# Task_10_1DHD.net
KiCad netlist of a schematic drawn in EasyEDA
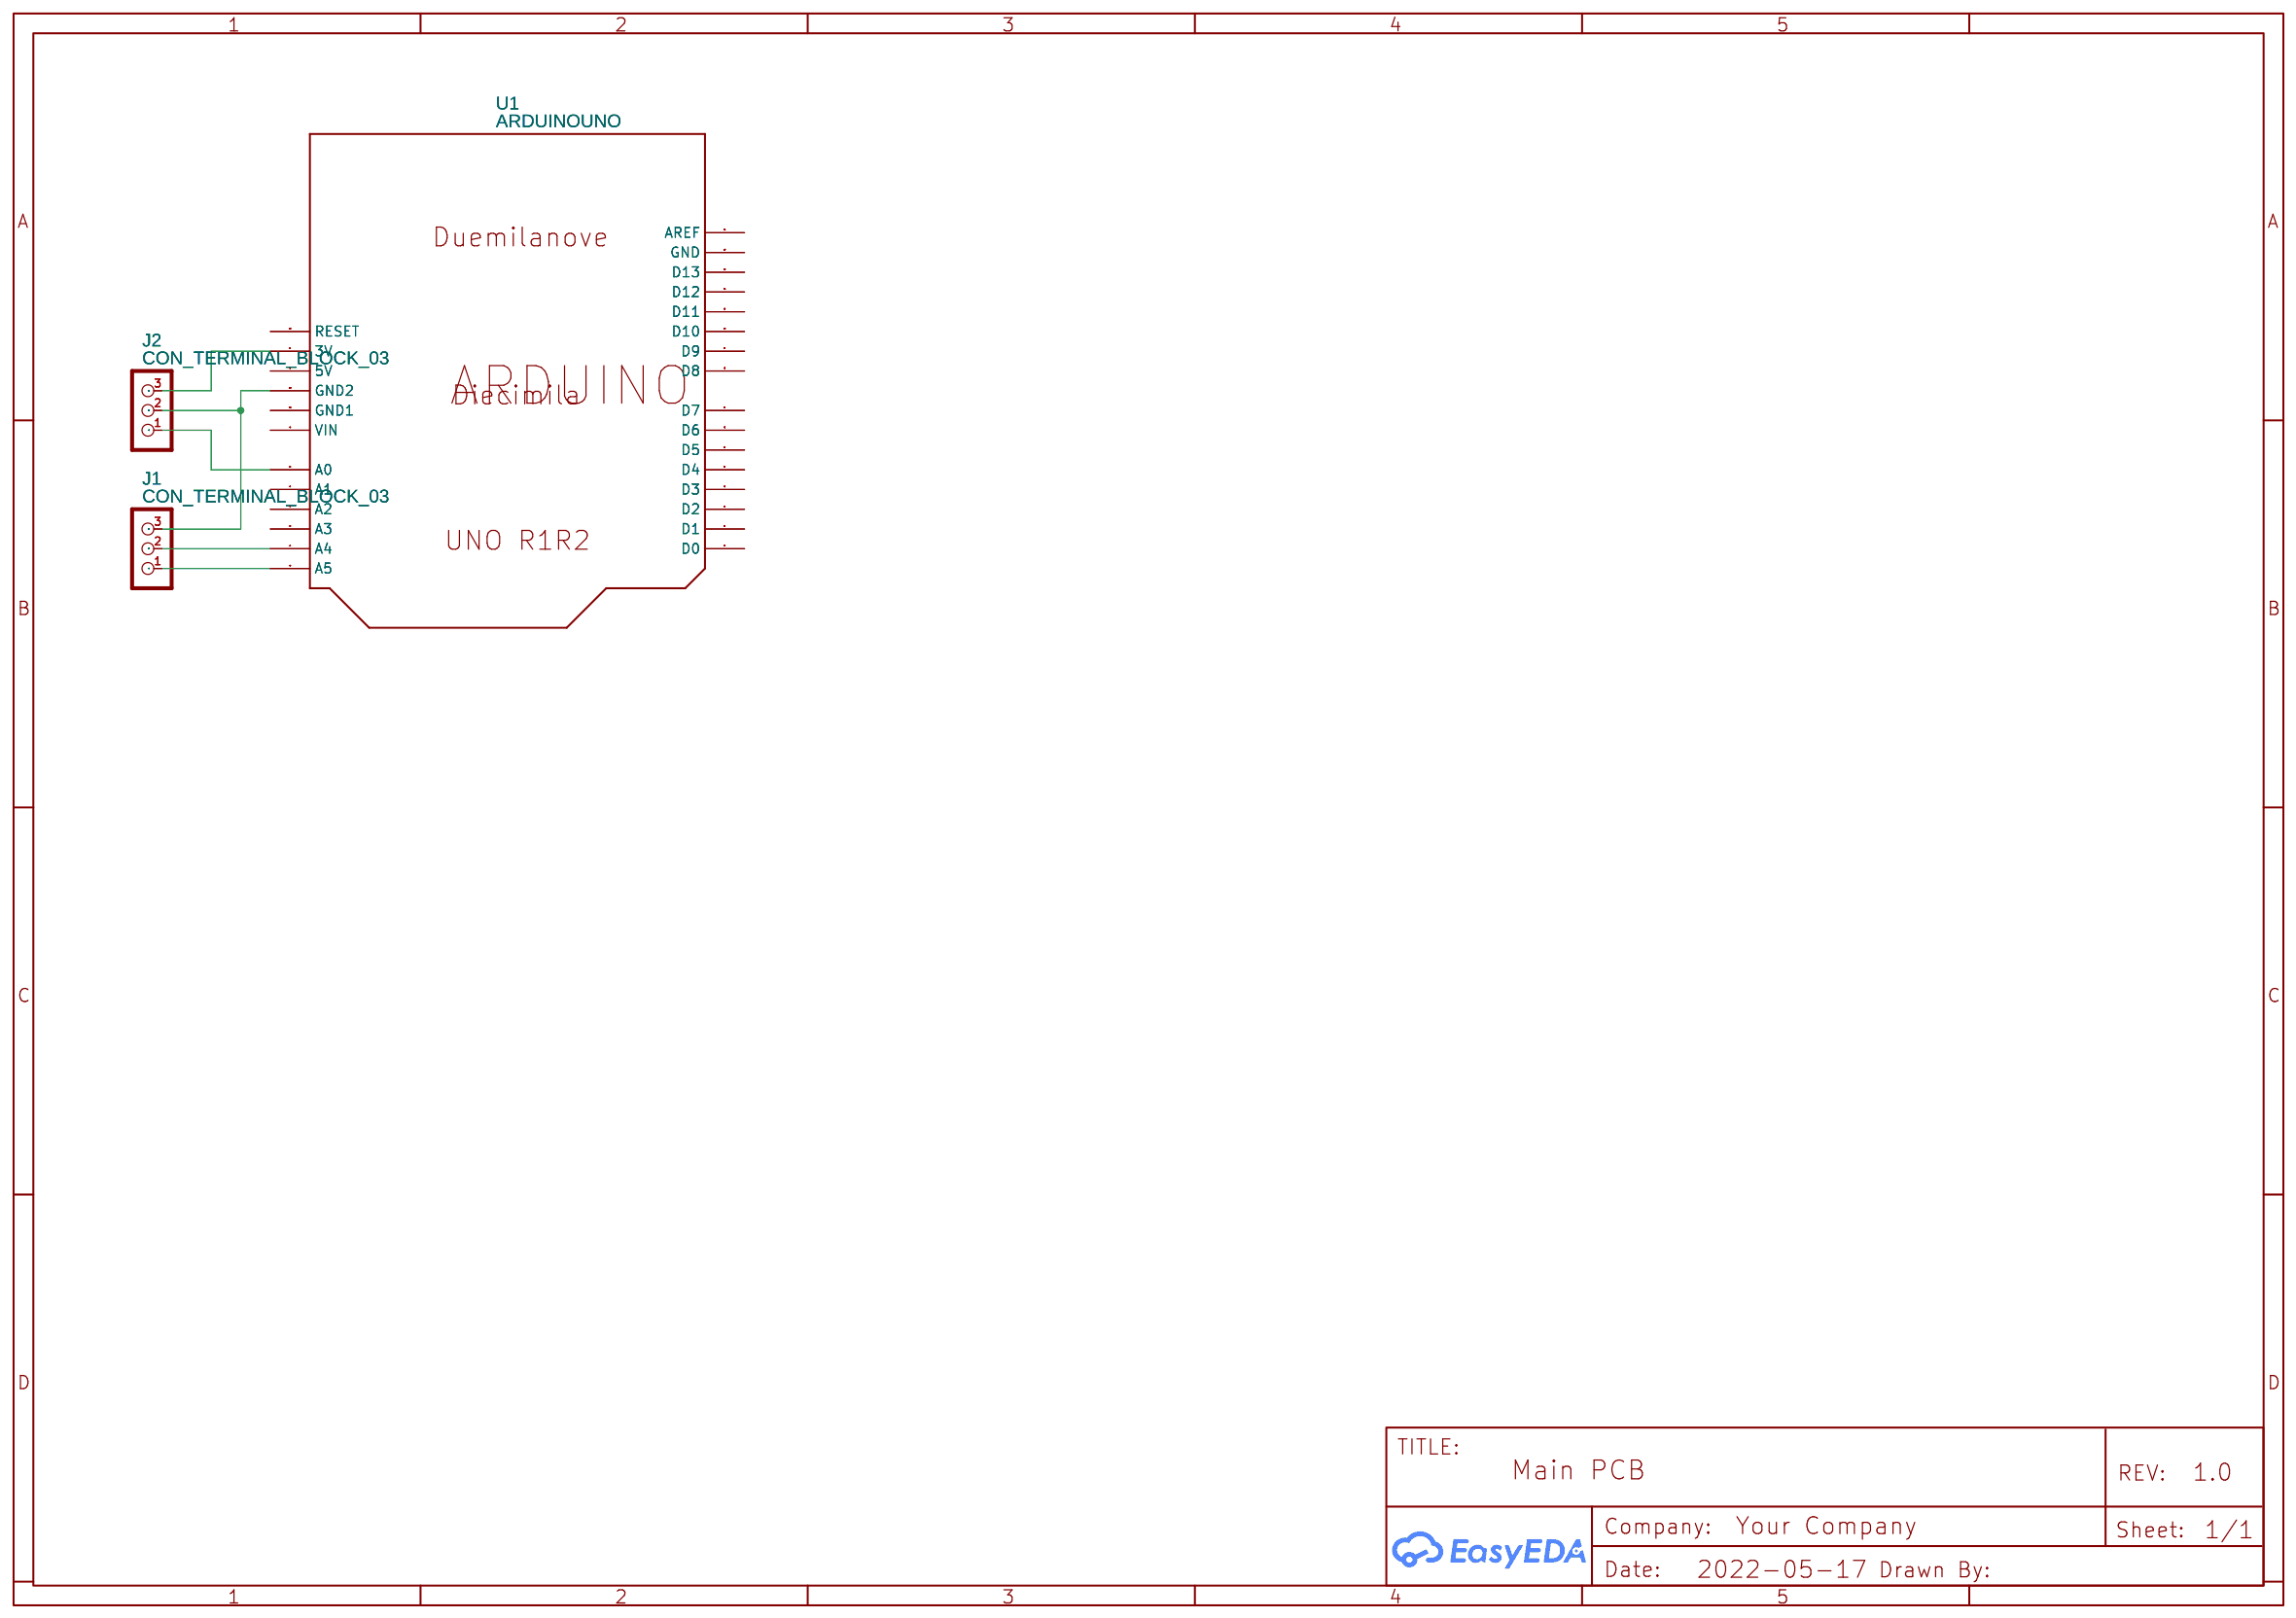
[diagram p0: Uno-SM Sensor]
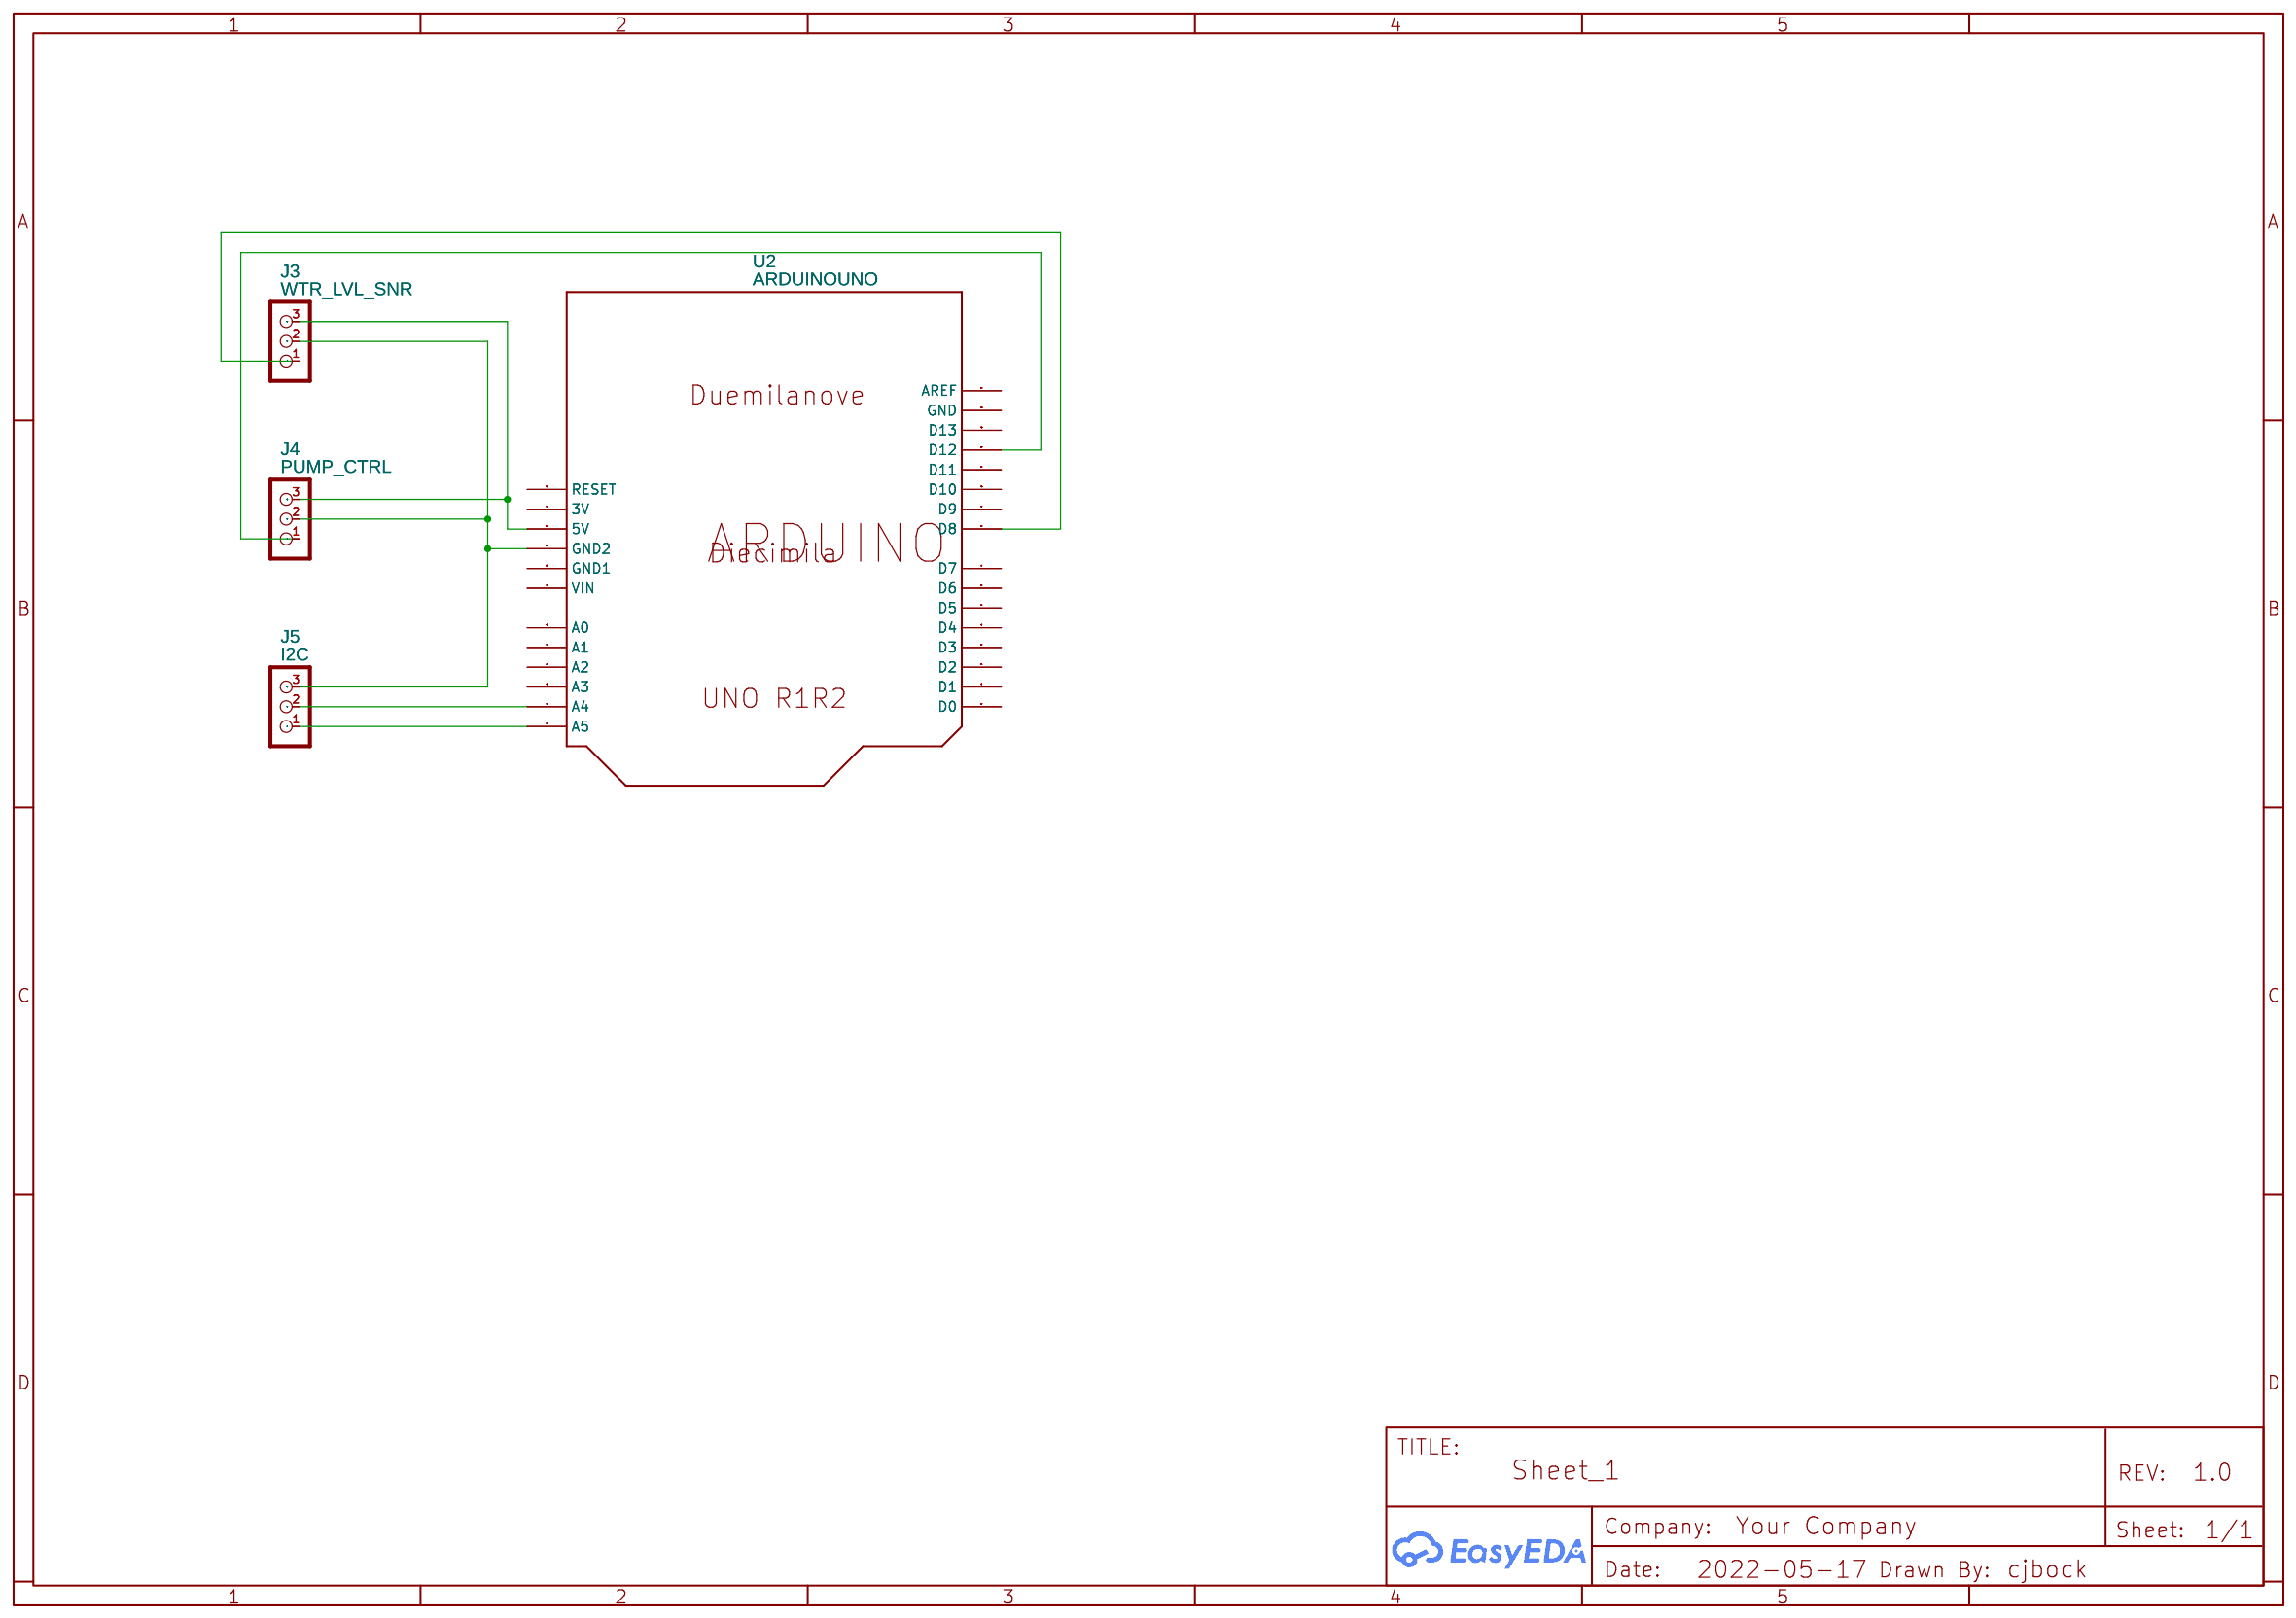
[diagram p1: Uno-Pump]
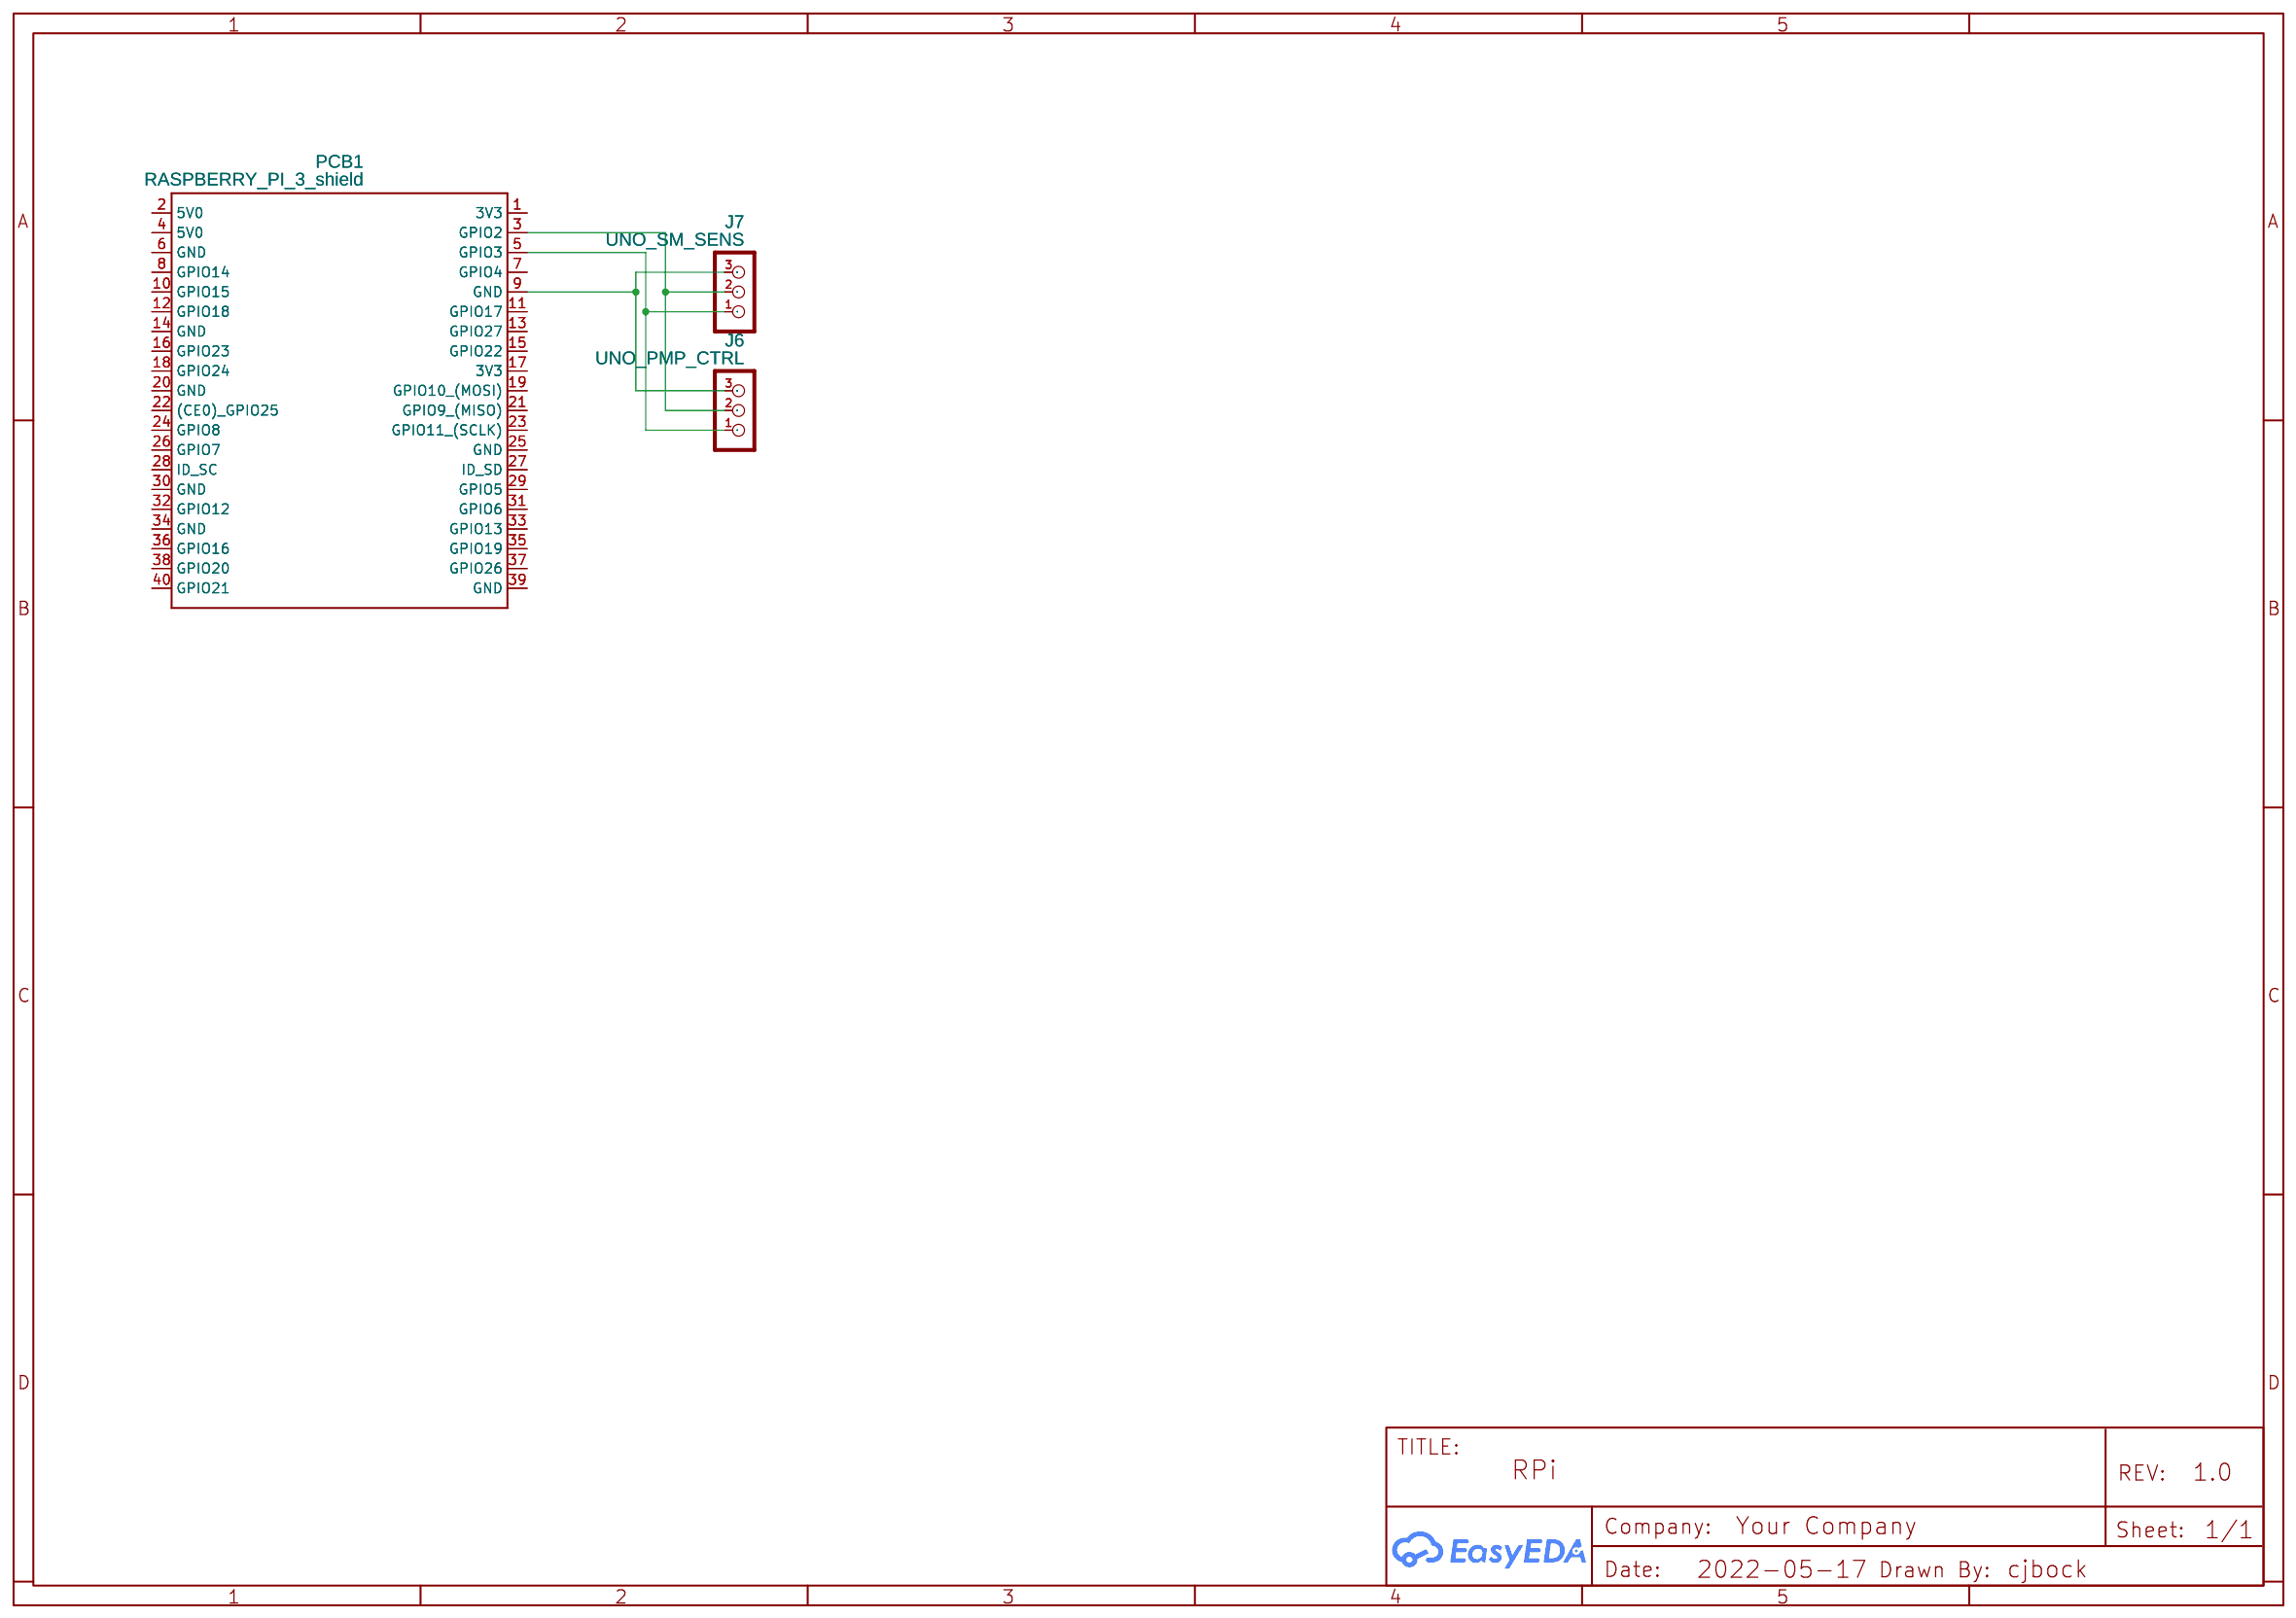
[diagram p2: RPI-Board]

(export (version "E")
  (design (tool "Eeschema 10.0.6"))
  (components
    (comp (ref "J1") (value "CON_TERMINAL_BLOCK_03") (libsource (lib "") (part "CON_TERMINAL_BLOCK_03")))
    (comp (ref "J2") (value "CON_TERMINAL_BLOCK_03") (libsource (lib "") (part "CON_TERMINAL_BLOCK_03")))
    (comp (ref "U1") (value "ARDUINOUNO") (libsource (lib "") (part "ARDUINOUNO")))
    (comp (ref "J3") (value "WTR_LVL_SNR") (libsource (lib "") (part "CON_TERMINAL_BLOCK_03-5MM")))
    (comp (ref "J4") (value "PUMP_CTRL") (libsource (lib "") (part "CON_TERMINAL_BLOCK_03-5MM")))
    (comp (ref "J5") (value "I2C") (libsource (lib "") (part "CON_TERMINAL_BLOCK_03-5MM")))
    (comp (ref "U2") (value "ARDUINOUNO") (libsource (lib "") (part "ARDUINOUNO")))
    (comp (ref "J6") (value "UNO_PMP_CTRL") (libsource (lib "") (part "CON_TERMINAL_BLOCK_03-5MM")))
    (comp (ref "J7") (value "UNO_SM_SENS") (libsource (lib "") (part "CON_TERMINAL_BLOCK_03-5MM")))
    (comp (ref "PCB1") (value "RASPBERRY_PI_3_shield") (libsource (lib "") (part "RASPBERRY_PI_3_shield")))
  )
  (nets
    (net (code "1") (name "Net-(J1-Pad1)") (class "Default")
      (node (ref "J1") (pin "1") (pinfunction "1_1") (pintype "unspecified"))
      (node (ref "U1") (pin "A5") (pinfunction "A5_A5") (pintype "unspecified"))
    )
    (net (code "2") (name "Net-(J1-Pad2)") (class "Default")
      (node (ref "J1") (pin "2") (pinfunction "2_2") (pintype "unspecified"))
      (node (ref "U1") (pin "A4") (pinfunction "A4_A4") (pintype "unspecified"))
    )
    (net (code "3") (name "Net-(J1-Pad3)") (class "Default")
      (node (ref "J1") (pin "3") (pinfunction "3_3") (pintype "unspecified"))
      (node (ref "J2") (pin "2") (pinfunction "2_2") (pintype "unspecified"))
      (node (ref "U1") (pin "GND2") (pinfunction "GND2_GND2") (pintype "passive"))
    )
    (net (code "4") (name "Net-(J2-Pad1)") (class "Default")
      (node (ref "J2") (pin "1") (pinfunction "1_1") (pintype "unspecified"))
      (node (ref "U1") (pin "A0") (pinfunction "A0_A0") (pintype "unspecified"))
    )
    (net (code "5") (name "Net-(J2-Pad3)") (class "Default")
      (node (ref "J2") (pin "3") (pinfunction "3_3") (pintype "unspecified"))
      (node (ref "U1") (pin "3V") (pinfunction "3V_3V") (pintype "passive"))
    )
    (net (code "6") (name "Net-(J3-Pad1)") (class "Default")
      (node (ref "J3") (pin "1") (pinfunction "1_1") (pintype "unspecified"))
      (node (ref "U2") (pin "D8") (pinfunction "D8_D8") (pintype "unspecified"))
    )
    (net (code "7") (name "Net-(J3-Pad2)") (class "Default")
      (node (ref "J3") (pin "2") (pinfunction "2_2") (pintype "unspecified"))
      (node (ref "J4") (pin "2") (pinfunction "2_2") (pintype "unspecified"))
      (node (ref "J5") (pin "3") (pinfunction "3_3") (pintype "unspecified"))
      (node (ref "U2") (pin "GND2") (pinfunction "GND2_GND2") (pintype "passive"))
    )
    (net (code "8") (name "Net-(J3-Pad3)") (class "Default")
      (node (ref "J3") (pin "3") (pinfunction "3_3") (pintype "unspecified"))
      (node (ref "J4") (pin "3") (pinfunction "3_3") (pintype "unspecified"))
      (node (ref "U2") (pin "5V") (pinfunction "5V_5V") (pintype "passive"))
    )
    (net (code "9") (name "Net-(J4-Pad1)") (class "Default")
      (node (ref "J4") (pin "1") (pinfunction "1_1") (pintype "unspecified"))
      (node (ref "U2") (pin "D12") (pinfunction "D12_D12") (pintype "unspecified"))
    )
    (net (code "10") (name "Net-(J5-Pad1)") (class "Default")
      (node (ref "J5") (pin "1") (pinfunction "1_1") (pintype "unspecified"))
      (node (ref "U2") (pin "A5") (pinfunction "A5_A5") (pintype "unspecified"))
    )
    (net (code "11") (name "Net-(J5-Pad2)") (class "Default")
      (node (ref "J5") (pin "2") (pinfunction "2_2") (pintype "unspecified"))
      (node (ref "U2") (pin "A4") (pinfunction "A4_A4") (pintype "unspecified"))
    )
    (net (code "12") (name "Net-(J6-Pad3)") (class "Default")
      (node (ref "J6") (pin "3") (pinfunction "3_3") (pintype "unspecified"))
      (node (ref "J7") (pin "3") (pinfunction "3_3") (pintype "unspecified"))
      (node (ref "PCB1") (pin "9") (pinfunction "GND_9") (pintype "unspecified"))
    )
    (net (code "13") (name "Net-(PCB1-GPIO2)") (class "Default")
      (node (ref "J6") (pin "2") (pinfunction "2_2") (pintype "unspecified"))
      (node (ref "J7") (pin "2") (pinfunction "2_2") (pintype "unspecified"))
      (node (ref "PCB1") (pin "3") (pinfunction "GPIO2_3") (pintype "unspecified"))
    )
    (net (code "14") (name "Net-(PCB1-GPIO3)") (class "Default")
      (node (ref "J6") (pin "1") (pinfunction "1_1") (pintype "unspecified"))
      (node (ref "J7") (pin "1") (pinfunction "1_1") (pintype "unspecified"))
      (node (ref "PCB1") (pin "5") (pinfunction "GPIO3_5") (pintype "unspecified"))
    )
    (net (code "15") (name "unconnected-(PCB1-(CE0)_GPIO25-Pad22)") (class "Default")
      (node (ref "PCB1") (pin "22") (pinfunction "(CE0)_GPIO25_22") (pintype "unspecified"))
    )
    (net (code "16") (name "unconnected-(PCB1-3V3-Pad1)") (class "Default")
      (node (ref "PCB1") (pin "1") (pinfunction "3V3_1") (pintype "unspecified"))
    )
    (net (code "17") (name "unconnected-(PCB1-3V3-Pad17)") (class "Default")
      (node (ref "PCB1") (pin "17") (pinfunction "3V3_17") (pintype "unspecified"))
    )
    (net (code "18") (name "unconnected-(PCB1-5V0-Pad2)") (class "Default")
      (node (ref "PCB1") (pin "2") (pinfunction "5V0_2") (pintype "unspecified"))
    )
    (net (code "19") (name "unconnected-(PCB1-5V0-Pad4)") (class "Default")
      (node (ref "PCB1") (pin "4") (pinfunction "5V0_4") (pintype "unspecified"))
    )
    (net (code "20") (name "unconnected-(PCB1-GND-Pad6)") (class "Default")
      (node (ref "PCB1") (pin "6") (pinfunction "GND_6") (pintype "unspecified"))
    )
    (net (code "21") (name "unconnected-(PCB1-GND-Pad14)") (class "Default")
      (node (ref "PCB1") (pin "14") (pinfunction "GND_14") (pintype "unspecified"))
    )
    (net (code "22") (name "unconnected-(PCB1-GND-Pad20)") (class "Default")
      (node (ref "PCB1") (pin "20") (pinfunction "GND_20") (pintype "unspecified"))
    )
    (net (code "23") (name "unconnected-(PCB1-GND-Pad25)") (class "Default")
      (node (ref "PCB1") (pin "25") (pinfunction "GND_25") (pintype "unspecified"))
    )
    (net (code "24") (name "unconnected-(PCB1-GND-Pad30)") (class "Default")
      (node (ref "PCB1") (pin "30") (pinfunction "GND_30") (pintype "unspecified"))
    )
    (net (code "25") (name "unconnected-(PCB1-GND-Pad34)") (class "Default")
      (node (ref "PCB1") (pin "34") (pinfunction "GND_34") (pintype "unspecified"))
    )
    (net (code "26") (name "unconnected-(PCB1-GND-Pad39)") (class "Default")
      (node (ref "PCB1") (pin "39") (pinfunction "GND_39") (pintype "unspecified"))
    )
    (net (code "27") (name "unconnected-(PCB1-GPIO4-Pad7)") (class "Default")
      (node (ref "PCB1") (pin "7") (pinfunction "GPIO4_7") (pintype "unspecified"))
    )
    (net (code "28") (name "unconnected-(PCB1-GPIO5-Pad29)") (class "Default")
      (node (ref "PCB1") (pin "29") (pinfunction "GPIO5_29") (pintype "unspecified"))
    )
    (net (code "29") (name "unconnected-(PCB1-GPIO6-Pad31)") (class "Default")
      (node (ref "PCB1") (pin "31") (pinfunction "GPIO6_31") (pintype "unspecified"))
    )
    (net (code "30") (name "unconnected-(PCB1-GPIO7-Pad26)") (class "Default")
      (node (ref "PCB1") (pin "26") (pinfunction "GPIO7_26") (pintype "unspecified"))
    )
    (net (code "31") (name "unconnected-(PCB1-GPIO8-Pad24)") (class "Default")
      (node (ref "PCB1") (pin "24") (pinfunction "GPIO8_24") (pintype "unspecified"))
    )
    (net (code "32") (name "unconnected-(PCB1-GPIO9_(MISO)-Pad21)") (class "Default")
      (node (ref "PCB1") (pin "21") (pinfunction "GPIO9_(MISO)_21") (pintype "unspecified"))
    )
    (net (code "33") (name "unconnected-(PCB1-GPIO10_(MOSI)-Pad19)") (class "Default")
      (node (ref "PCB1") (pin "19") (pinfunction "GPIO10_(MOSI)_19") (pintype "unspecified"))
    )
    (net (code "34") (name "unconnected-(PCB1-GPIO11_(SCLK)-Pad23)") (class "Default")
      (node (ref "PCB1") (pin "23") (pinfunction "GPIO11_(SCLK)_23") (pintype "unspecified"))
    )
    (net (code "35") (name "unconnected-(PCB1-GPIO12-Pad32)") (class "Default")
      (node (ref "PCB1") (pin "32") (pinfunction "GPIO12_32") (pintype "unspecified"))
    )
    (net (code "36") (name "unconnected-(PCB1-GPIO13-Pad33)") (class "Default")
      (node (ref "PCB1") (pin "33") (pinfunction "GPIO13_33") (pintype "unspecified"))
    )
    (net (code "37") (name "unconnected-(PCB1-GPIO14-Pad8)") (class "Default")
      (node (ref "PCB1") (pin "8") (pinfunction "GPIO14_8") (pintype "unspecified"))
    )
    (net (code "38") (name "unconnected-(PCB1-GPIO15-Pad10)") (class "Default")
      (node (ref "PCB1") (pin "10") (pinfunction "GPIO15_10") (pintype "unspecified"))
    )
    (net (code "39") (name "unconnected-(PCB1-GPIO16-Pad36)") (class "Default")
      (node (ref "PCB1") (pin "36") (pinfunction "GPIO16_36") (pintype "unspecified"))
    )
    (net (code "40") (name "unconnected-(PCB1-GPIO17-Pad11)") (class "Default")
      (node (ref "PCB1") (pin "11") (pinfunction "GPIO17_11") (pintype "unspecified"))
    )
    (net (code "41") (name "unconnected-(PCB1-GPIO18-Pad12)") (class "Default")
      (node (ref "PCB1") (pin "12") (pinfunction "GPIO18_12") (pintype "unspecified"))
    )
    (net (code "42") (name "unconnected-(PCB1-GPIO19-Pad35)") (class "Default")
      (node (ref "PCB1") (pin "35") (pinfunction "GPIO19_35") (pintype "unspecified"))
    )
    (net (code "43") (name "unconnected-(PCB1-GPIO20-Pad38)") (class "Default")
      (node (ref "PCB1") (pin "38") (pinfunction "GPIO20_38") (pintype "unspecified"))
    )
    (net (code "44") (name "unconnected-(PCB1-GPIO21-Pad40)") (class "Default")
      (node (ref "PCB1") (pin "40") (pinfunction "GPIO21_40") (pintype "unspecified"))
    )
    (net (code "45") (name "unconnected-(PCB1-GPIO22-Pad15)") (class "Default")
      (node (ref "PCB1") (pin "15") (pinfunction "GPIO22_15") (pintype "unspecified"))
    )
    (net (code "46") (name "unconnected-(PCB1-GPIO23-Pad16)") (class "Default")
      (node (ref "PCB1") (pin "16") (pinfunction "GPIO23_16") (pintype "unspecified"))
    )
    (net (code "47") (name "unconnected-(PCB1-GPIO24-Pad18)") (class "Default")
      (node (ref "PCB1") (pin "18") (pinfunction "GPIO24_18") (pintype "unspecified"))
    )
    (net (code "48") (name "unconnected-(PCB1-GPIO26-Pad37)") (class "Default")
      (node (ref "PCB1") (pin "37") (pinfunction "GPIO26_37") (pintype "unspecified"))
    )
    (net (code "49") (name "unconnected-(PCB1-GPIO27-Pad13)") (class "Default")
      (node (ref "PCB1") (pin "13") (pinfunction "GPIO27_13") (pintype "unspecified"))
    )
    (net (code "50") (name "unconnected-(PCB1-ID_SC-Pad28)") (class "Default")
      (node (ref "PCB1") (pin "28") (pinfunction "ID_SC_28") (pintype "unspecified"))
    )
    (net (code "51") (name "unconnected-(PCB1-ID_SD-Pad27)") (class "Default")
      (node (ref "PCB1") (pin "27") (pinfunction "ID_SD_27") (pintype "unspecified"))
    )
    (net (code "52") (name "unconnected-(U1-Pad5V)") (class "Default")
      (node (ref "U1") (pin "5V") (pinfunction "5V_5V") (pintype "passive"))
    )
    (net (code "53") (name "unconnected-(U1-PadA1)") (class "Default")
      (node (ref "U1") (pin "A1") (pinfunction "A1_A1") (pintype "unspecified"))
    )
    (net (code "54") (name "unconnected-(U1-PadA2)") (class "Default")
      (node (ref "U1") (pin "A2") (pinfunction "A2_A2") (pintype "unspecified"))
    )
    (net (code "55") (name "unconnected-(U1-PadA3)") (class "Default")
      (node (ref "U1") (pin "A3") (pinfunction "A3_A3") (pintype "unspecified"))
    )
    (net (code "56") (name "unconnected-(U1-PadAREF)") (class "Default")
      (node (ref "U1") (pin "AREF") (pinfunction "AREF_AREF") (pintype "unspecified"))
    )
    (net (code "57") (name "unconnected-(U1-PadD0)") (class "Default")
      (node (ref "U1") (pin "D0") (pinfunction "D0_D0") (pintype "unspecified"))
    )
    (net (code "58") (name "unconnected-(U1-PadD1)") (class "Default")
      (node (ref "U1") (pin "D1") (pinfunction "D1_D1") (pintype "unspecified"))
    )
    (net (code "59") (name "unconnected-(U1-PadD2)") (class "Default")
      (node (ref "U1") (pin "D2") (pinfunction "D2_D2") (pintype "unspecified"))
    )
    (net (code "60") (name "unconnected-(U1-PadD3)") (class "Default")
      (node (ref "U1") (pin "D3") (pinfunction "D3_D3") (pintype "unspecified"))
    )
    (net (code "61") (name "unconnected-(U1-PadD4)") (class "Default")
      (node (ref "U1") (pin "D4") (pinfunction "D4_D4") (pintype "unspecified"))
    )
    (net (code "62") (name "unconnected-(U1-PadD5)") (class "Default")
      (node (ref "U1") (pin "D5") (pinfunction "D5_D5") (pintype "unspecified"))
    )
    (net (code "63") (name "unconnected-(U1-PadD6)") (class "Default")
      (node (ref "U1") (pin "D6") (pinfunction "D6_D6") (pintype "unspecified"))
    )
    (net (code "64") (name "unconnected-(U1-PadD7)") (class "Default")
      (node (ref "U1") (pin "D7") (pinfunction "D7_D7") (pintype "unspecified"))
    )
    (net (code "65") (name "unconnected-(U1-PadD8)") (class "Default")
      (node (ref "U1") (pin "D8") (pinfunction "D8_D8") (pintype "unspecified"))
    )
    (net (code "66") (name "unconnected-(U1-PadD9)") (class "Default")
      (node (ref "U1") (pin "D9") (pinfunction "D9_D9") (pintype "unspecified"))
    )
    (net (code "67") (name "unconnected-(U1-PadD10)") (class "Default")
      (node (ref "U1") (pin "D10") (pinfunction "D10_D10") (pintype "unspecified"))
    )
    (net (code "68") (name "unconnected-(U1-PadD11)") (class "Default")
      (node (ref "U1") (pin "D11") (pinfunction "D11_D11") (pintype "unspecified"))
    )
    (net (code "69") (name "unconnected-(U1-PadD12)") (class "Default")
      (node (ref "U1") (pin "D12") (pinfunction "D12_D12") (pintype "unspecified"))
    )
    (net (code "70") (name "unconnected-(U1-PadD13)") (class "Default")
      (node (ref "U1") (pin "D13") (pinfunction "D13_D13") (pintype "unspecified"))
    )
    (net (code "71") (name "unconnected-(U1-PadGND)") (class "Default")
      (node (ref "U1") (pin "GND") (pinfunction "GND_GND") (pintype "passive"))
    )
    (net (code "72") (name "unconnected-(U1-PadGND1)") (class "Default")
      (node (ref "U1") (pin "GND1") (pinfunction "GND1_GND1") (pintype "passive"))
    )
    (net (code "73") (name "unconnected-(U1-PadRESET)") (class "Default")
      (node (ref "U1") (pin "RESET") (pinfunction "RESET_RESET") (pintype "unspecified"))
    )
    (net (code "74") (name "unconnected-(U1-PadVIN)") (class "Default")
      (node (ref "U1") (pin "VIN") (pinfunction "VIN_VIN") (pintype "passive"))
    )
    (net (code "75") (name "unconnected-(U2-Pad3V)") (class "Default")
      (node (ref "U2") (pin "3V") (pinfunction "3V_3V") (pintype "passive"))
    )
    (net (code "76") (name "unconnected-(U2-PadA0)") (class "Default")
      (node (ref "U2") (pin "A0") (pinfunction "A0_A0") (pintype "unspecified"))
    )
    (net (code "77") (name "unconnected-(U2-PadA1)") (class "Default")
      (node (ref "U2") (pin "A1") (pinfunction "A1_A1") (pintype "unspecified"))
    )
    (net (code "78") (name "unconnected-(U2-PadA2)") (class "Default")
      (node (ref "U2") (pin "A2") (pinfunction "A2_A2") (pintype "unspecified"))
    )
    (net (code "79") (name "unconnected-(U2-PadA3)") (class "Default")
      (node (ref "U2") (pin "A3") (pinfunction "A3_A3") (pintype "unspecified"))
    )
    (net (code "80") (name "unconnected-(U2-PadAREF)") (class "Default")
      (node (ref "U2") (pin "AREF") (pinfunction "AREF_AREF") (pintype "unspecified"))
    )
    (net (code "81") (name "unconnected-(U2-PadD0)") (class "Default")
      (node (ref "U2") (pin "D0") (pinfunction "D0_D0") (pintype "unspecified"))
    )
    (net (code "82") (name "unconnected-(U2-PadD1)") (class "Default")
      (node (ref "U2") (pin "D1") (pinfunction "D1_D1") (pintype "unspecified"))
    )
    (net (code "83") (name "unconnected-(U2-PadD2)") (class "Default")
      (node (ref "U2") (pin "D2") (pinfunction "D2_D2") (pintype "unspecified"))
    )
    (net (code "84") (name "unconnected-(U2-PadD3)") (class "Default")
      (node (ref "U2") (pin "D3") (pinfunction "D3_D3") (pintype "unspecified"))
    )
    (net (code "85") (name "unconnected-(U2-PadD4)") (class "Default")
      (node (ref "U2") (pin "D4") (pinfunction "D4_D4") (pintype "unspecified"))
    )
    (net (code "86") (name "unconnected-(U2-PadD5)") (class "Default")
      (node (ref "U2") (pin "D5") (pinfunction "D5_D5") (pintype "unspecified"))
    )
    (net (code "87") (name "unconnected-(U2-PadD6)") (class "Default")
      (node (ref "U2") (pin "D6") (pinfunction "D6_D6") (pintype "unspecified"))
    )
    (net (code "88") (name "unconnected-(U2-PadD7)") (class "Default")
      (node (ref "U2") (pin "D7") (pinfunction "D7_D7") (pintype "unspecified"))
    )
    (net (code "89") (name "unconnected-(U2-PadD9)") (class "Default")
      (node (ref "U2") (pin "D9") (pinfunction "D9_D9") (pintype "unspecified"))
    )
    (net (code "90") (name "unconnected-(U2-PadD10)") (class "Default")
      (node (ref "U2") (pin "D10") (pinfunction "D10_D10") (pintype "unspecified"))
    )
    (net (code "91") (name "unconnected-(U2-PadD11)") (class "Default")
      (node (ref "U2") (pin "D11") (pinfunction "D11_D11") (pintype "unspecified"))
    )
    (net (code "92") (name "unconnected-(U2-PadD13)") (class "Default")
      (node (ref "U2") (pin "D13") (pinfunction "D13_D13") (pintype "unspecified"))
    )
    (net (code "93") (name "unconnected-(U2-PadGND)") (class "Default")
      (node (ref "U2") (pin "GND") (pinfunction "GND_GND") (pintype "passive"))
    )
    (net (code "94") (name "unconnected-(U2-PadGND1)") (class "Default")
      (node (ref "U2") (pin "GND1") (pinfunction "GND1_GND1") (pintype "passive"))
    )
    (net (code "95") (name "unconnected-(U2-PadRESET)") (class "Default")
      (node (ref "U2") (pin "RESET") (pinfunction "RESET_RESET") (pintype "unspecified"))
    )
    (net (code "96") (name "unconnected-(U2-PadVIN)") (class "Default")
      (node (ref "U2") (pin "VIN") (pinfunction "VIN_VIN") (pintype "passive"))
    )
  )
)
